# Regulator.net
KiCad netlist of a schematic drawn in Altium Designer
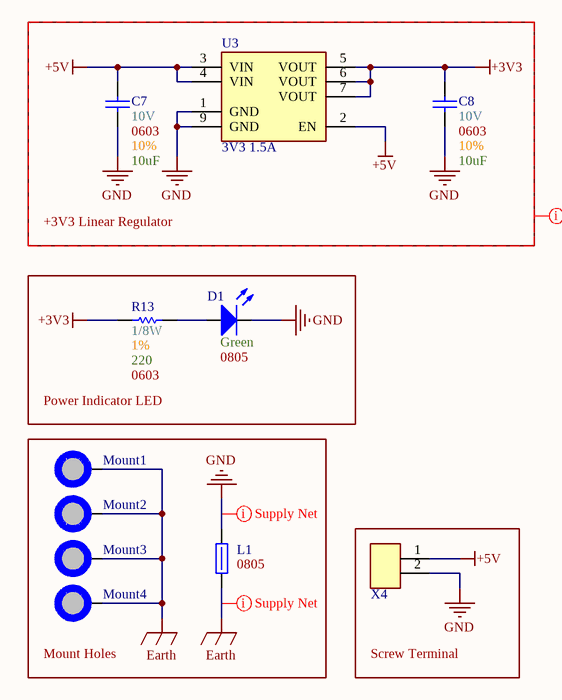
[diagram p0: Regulator.SchDoc]

(export (version "E")
  (design (tool "Eeschema 10.0.6"))
  (components
    (comp (ref "C7")
      (value "[Cap] 0603 10uF 10% 10V")
      (footprint "[Cap] SMD 0603")
      (description "CL10A106KP8NNNC")
      (fields
        (field (name "MAX VOLTAGE") "10V")
        (field (name "SIZE PACKAGE") "0603")
        (field (name "TOLERANCE") "10%")
        (field (name "CAPACITANCE") "10uF")
      )
      (libsource (lib "Capacitors") (part "[Cap] 0603 10uF 10% 10V"))
    )
    (comp (ref "C8")
      (value "[Cap] 0603 10uF 10% 10V")
      (footprint "[Cap] SMD 0603")
      (description "CL10A106KP8NNNC")
      (fields
        (field (name "MAX VOLTAGE") "10V")
        (field (name "SIZE PACKAGE") "0603")
        (field (name "TOLERANCE") "10%")
        (field (name "CAPACITANCE") "10uF")
      )
      (libsource (lib "Capacitors") (part "[Cap] 0603 10uF 10% 10V"))
    )
    (comp (ref "D1")
      (value "[LED] SMD 0805 Green")
      (footprint "[LED] SMD 0805")
      (description "LG R971-KN-1-0-20-R18")
      (fields (field (name "COLOR") "Green") (field (name "SIZE PACKAGE") "0805"))
      (libsource (lib "LEDs") (part "[LED] SMD 0805 Green"))
    )
    (comp (ref "L1")
      (value "652-MH2029-300Y")
      (footprint "[Ferrite] SMD 0805")
      (fields (field (name "SIZE PACKAGE") "0805"))
      (libsource (lib "Ferrite Beads") (part "[Ferrite] SMD 0805 3A 30ohm"))
    )
    (comp (ref "Mount1")
      (value "M3 Mount Hole")
      (footprint "[Mount] M3 Mount Hole")
      (description "Place at least 4.5mm from board edge. Plated.")
      (libsource (lib "RADM Connectors") (part "[Mount] M3 Mount Hole"))
    )
    (comp (ref "Mount2")
      (value "M3 Mount Hole")
      (footprint "[Mount] M3 Mount Hole")
      (description "Place at least 4.5mm from board edge. Plated.")
      (libsource (lib "RADM Connectors") (part "[Mount] M3 Mount Hole"))
    )
    (comp (ref "Mount3")
      (value "M3 Mount Hole")
      (footprint "[Mount] M3 Mount Hole")
      (description "Place at least 4.5mm from board edge. Plated.")
      (libsource (lib "RADM Connectors") (part "[Mount] M3 Mount Hole"))
    )
    (comp (ref "Mount4")
      (value "M3 Mount Hole")
      (footprint "[Mount] M3 Mount Hole")
      (description "Place at least 4.5mm from board edge. Plated.")
      (libsource (lib "RADM Connectors") (part "[Mount] M3 Mount Hole"))
    )
    (comp (ref "R13")
      (value "[220] SMD 0603 1% 1/10W")
      (footprint "[Res] SMD 0603")
      (description "CRGCQ0805F220R")
      (fields
        (field (name "WATTAGE") "1/8W")
        (field (name "TOLERANCE") "1%")
        (field (name "RESISTANCE") "220")
        (field (name "SIZE PACKAGE") "0603")
      )
      (libsource (lib "Resistors") (part "[220] SMD 0603 1% 1/10W"))
    )
    (comp (ref "U3")
      (value "3V3 1.5A")
      (footprint "[Linear] 3V3 1.5A")
      (description "AP7362A-33SP-13")
      (libsource (lib "Voltage Regulators") (part "[Linear] 3V3 1.5A"))
    )
    (comp (ref "X4")
      (value "2pin Screw Terminal")
      (footprint "[Screw Terminal] 2pin 5mm")
      (description "TB002-500-02BE")
      (libsource (lib "Connectors") (part "[Screw Terminal] 2pin"))
    )
  )
  (nets
    (net (code "1") (name "+3V3") (class "Default")
      (node (ref "C8") (pin "2") (pinfunction "2_2") (pintype "passive"))
      (node (ref "R13") (pin "1") (pinfunction "1_1") (pintype "passive"))
      (node (ref "U3") (pin "5") (pinfunction "VOUT_5") (pintype "passive"))
      (node (ref "U3") (pin "6") (pinfunction "VOUT_6") (pintype "passive"))
      (node (ref "U3") (pin "7") (pinfunction "VOUT_7") (pintype "passive"))
    )
    (net (code "2") (name "+5V") (class "Default")
      (node (ref "C7") (pin "2") (pinfunction "2_2") (pintype "passive"))
      (node (ref "U3") (pin "2") (pinfunction "EN_2") (pintype "passive"))
      (node (ref "U3") (pin "3") (pinfunction "VIN_3") (pintype "passive"))
      (node (ref "U3") (pin "4") (pinfunction "VIN_4") (pintype "passive"))
      (node (ref "X4") (pin "1") (pintype "power_in"))
    )
    (net (code "3") (name "Earth") (class "Default")
      (node (ref "L1") (pin "1") (pinfunction "1_1") (pintype "passive"))
      (node (ref "Mount1") (pin "1") (pintype "power_in"))
      (node (ref "Mount2") (pin "1") (pintype "power_in"))
      (node (ref "Mount3") (pin "1") (pintype "power_in"))
      (node (ref "Mount4") (pin "1") (pintype "power_in"))
    )
    (net (code "4") (name "GND") (class "Default")
      (node (ref "C7") (pin "1") (pinfunction "1_1") (pintype "passive"))
      (node (ref "C8") (pin "1") (pinfunction "1_1") (pintype "passive"))
      (node (ref "D1") (pin "2") (pinfunction "Cathode_2") (pintype "passive"))
      (node (ref "L1") (pin "2") (pinfunction "2_2") (pintype "passive"))
      (node (ref "U3") (pin "1") (pinfunction "GND_1") (pintype "passive"))
      (node (ref "U3") (pin "9") (pinfunction "GND_9") (pintype "passive"))
      (node (ref "X4") (pin "2") (pintype "power_in"))
    )
    (net (code "5") (name "Net-(D1-Anode)") (class "Default")
      (node (ref "D1") (pin "1") (pinfunction "Anode_1") (pintype "passive"))
      (node (ref "R13") (pin "2") (pinfunction "2_2") (pintype "passive"))
    )
  )
)
